# Rectifier.net
KiCad netlist of a schematic drawn in Altium Designer
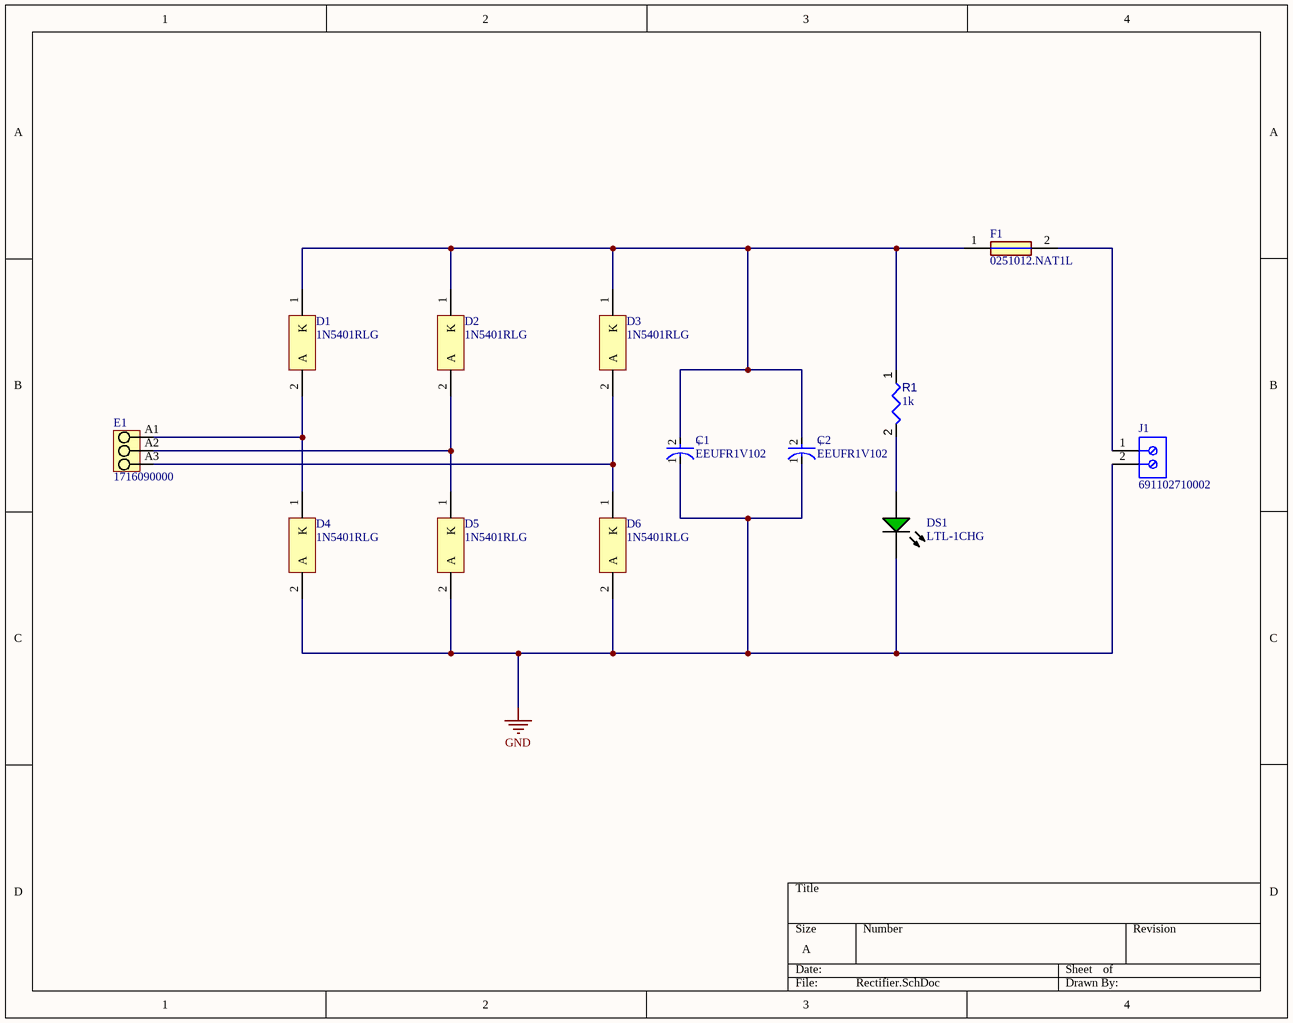
[diagram p0: Rectifier.SchDoc]

(export (version "E")
  (design (tool "Eeschema 10.0.6"))
  (components
    (comp (ref "C1")
      (value "EEUFR1V102")
      (footprint "FP-RAD-TH-D_12_5_0_5-L_20-MFG")
      (description "Aluminum Electrolytic Capacitors (Radial Lead Type) 1000uF ±20% 35V")
      (fields (field (name "TOLERANCE") "20%") (field (name "VOLTAGE") "35V"))
      (libsource (lib "Altium Content Vault") (part "a00bbbee19879c290e62620ae7e47b1"))
    )
    (comp (ref "C2")
      (value "EEUFR1V102")
      (footprint "FP-RAD-TH-D_12_5_0_5-L_20-MFG")
      (description "Aluminum Electrolytic Capacitors (Radial Lead Type) 1000uF ±20% 35V")
      (fields (field (name "TOLERANCE") "20%") (field (name "VOLTAGE") "35V"))
      (libsource (lib "Altium Content Vault") (part "a00bbbee19879c290e62620ae7e47b1"))
    )
    (comp (ref "D1")
      (value "1N5401RLG")
      (footprint "ONSC-AXIAL_LEAD-2-267-05_V")
      (description "Standard Recovery Rectifier, 2-Pin Axial_Lead, Pb-Free, Tape and Reel")
      (fields (field (name "MANUFACTURER") "On Semiconductor"))
      (libsource (lib "Altium Content Vault") (part "ONSC-D-K1A2-2_A"))
    )
    (comp (ref "D2")
      (value "1N5401RLG")
      (footprint "ONSC-AXIAL_LEAD-2-267-05_V")
      (description "Standard Recovery Rectifier, 2-Pin Axial_Lead, Pb-Free, Tape and Reel")
      (fields (field (name "MANUFACTURER") "On Semiconductor"))
      (libsource (lib "Altium Content Vault") (part "ONSC-D-K1A2-2_A"))
    )
    (comp (ref "D3")
      (value "1N5401RLG")
      (footprint "ONSC-AXIAL_LEAD-2-267-05_V")
      (description "Standard Recovery Rectifier, 2-Pin Axial_Lead, Pb-Free, Tape and Reel")
      (fields (field (name "MANUFACTURER") "On Semiconductor"))
      (libsource (lib "Altium Content Vault") (part "ONSC-D-K1A2-2_A"))
    )
    (comp (ref "D4")
      (value "1N5401RLG")
      (footprint "ONSC-AXIAL_LEAD-2-267-05_V")
      (description "Standard Recovery Rectifier, 2-Pin Axial_Lead, Pb-Free, Tape and Reel")
      (fields (field (name "MANUFACTURER") "On Semiconductor"))
      (libsource (lib "Altium Content Vault") (part "ONSC-D-K1A2-2_A"))
    )
    (comp (ref "D5")
      (value "1N5401RLG")
      (footprint "ONSC-AXIAL_LEAD-2-267-05_V")
      (description "Standard Recovery Rectifier, 2-Pin Axial_Lead, Pb-Free, Tape and Reel")
      (fields (field (name "MANUFACTURER") "On Semiconductor"))
      (libsource (lib "Altium Content Vault") (part "ONSC-D-K1A2-2_A"))
    )
    (comp (ref "D6")
      (value "1N5401RLG")
      (footprint "ONSC-AXIAL_LEAD-2-267-05_V")
      (description "Standard Recovery Rectifier, 2-Pin Axial_Lead, Pb-Free, Tape and Reel")
      (fields (field (name "MANUFACTURER") "On Semiconductor"))
      (libsource (lib "Altium Content Vault") (part "ONSC-D-K1A2-2_A"))
    )
    (comp (ref "DS1")
      (value "LTL-1CHG")
      (footprint "LTST-LTL-1CHG-2")
      (description "LED Uni-Color Green, 100 mW, 30 mA, -55 to 100 degC, 2-Pin THD, RoHS, Bulk")
      (fields (field (name "POWER") "100mW") (field (name "MANUFACTURER") "Lite-On"))
      (libsource (lib "Colton's Workspace") (part "LED-GREEN-AK-2"))
    )
    (comp (ref "E1")
      (value "1716090000")
      (footprint "LM_5_08_90_03")
      (description "OMNIMATE Signal - series LM")
      (fields (field (name "MANUFACTURER") "Weidmueller"))
      (libsource (lib "Altium Content Vault") (part "Terminal_03_1x03"))
    )
    (comp (ref "F1")
      (value "0251012.NAT1L")
      (footprint "SamacSys:0251012NAT1L")
      (description "Fuse")
      (libsource (lib "*") (part "0251012.NAT1L"))
    )
    (comp (ref "J1")
      (value "691102710002")
      (footprint "691102710002")
      (description "Series 102 - 5.00 mm Horizontal Entry Modular with Pressure Clamp WR-TBL, 2 pin")
      (fields (field (name "MANUFACTURER") "Wurth Elektronik") (field (name "PUBLISHER") "WurthElektronik"))
      (libsource (lib "Altium Content Vault") (part "WE-CN-1P-F-TB2"))
    )
    (comp (ref "R1")
      (value "1k")
      (footprint "RESA60-630X240")
      (description "Axial Resistor, 1 KOhm, +/- 1%, 250 mW, -55 to 155 degC, 2-Pin THD, RoHS, Bulk")
      (fields (field (name "TOLERANCE") "1%") (field (name "POWER") "250mW"))
      (libsource (lib "Colton's Workspace") (part "RES-2"))
    )
  )
  (nets
    (net (code "1") (name "GND") (class "Default")
      (node (ref "C1") (pin "1") (pinfunction "C_1") (pintype "passive"))
      (node (ref "C2") (pin "1") (pinfunction "C_1") (pintype "passive"))
      (node (ref "D4") (pin "2") (pinfunction "A_2") (pintype "passive"))
      (node (ref "D5") (pin "2") (pinfunction "A_2") (pintype "passive"))
      (node (ref "D6") (pin "2") (pinfunction "A_2") (pintype "passive"))
      (node (ref "DS1") (pin "2") (pinfunction "K_2") (pintype "passive"))
      (node (ref "J1") (pin "2") (pinfunction "2_2") (pintype "passive"))
    )
    (net (code "2") (name "Net-(C1-A)") (class "Default")
      (node (ref "C1") (pin "2") (pinfunction "A_2") (pintype "passive"))
      (node (ref "C2") (pin "2") (pinfunction "A_2") (pintype "passive"))
      (node (ref "D1") (pin "1") (pinfunction "K_1") (pintype "passive"))
      (node (ref "D2") (pin "1") (pinfunction "K_1") (pintype "passive"))
      (node (ref "D3") (pin "1") (pinfunction "K_1") (pintype "passive"))
      (node (ref "F1") (pin "1") (pinfunction "1_1") (pintype "passive"))
      (node (ref "R1") (pin "1") (pinfunction "1_1") (pintype "passive"))
    )
    (net (code "3") (name "Net-(D1-A)") (class "Default")
      (node (ref "D1") (pin "2") (pinfunction "A_2") (pintype "passive"))
      (node (ref "D4") (pin "1") (pinfunction "K_1") (pintype "passive"))
      (node (ref "E1") (pin "A1") (pinfunction "A1_A1") (pintype "passive"))
    )
    (net (code "4") (name "Net-(D2-A)") (class "Default")
      (node (ref "D2") (pin "2") (pinfunction "A_2") (pintype "passive"))
      (node (ref "D5") (pin "1") (pinfunction "K_1") (pintype "passive"))
      (node (ref "E1") (pin "A2") (pinfunction "A2_A2") (pintype "passive"))
    )
    (net (code "5") (name "Net-(D3-A)") (class "Default")
      (node (ref "D3") (pin "2") (pinfunction "A_2") (pintype "passive"))
      (node (ref "D6") (pin "1") (pinfunction "K_1") (pintype "passive"))
      (node (ref "E1") (pin "A3") (pinfunction "A3_A3") (pintype "passive"))
    )
    (net (code "6") (name "Net-(DS1-A)") (class "Default")
      (node (ref "DS1") (pin "1") (pinfunction "A_1") (pintype "passive"))
      (node (ref "R1") (pin "2") (pinfunction "2_2") (pintype "passive"))
    )
    (net (code "7") (name "Net-(F1-Pad2)") (class "Default")
      (node (ref "F1") (pin "2") (pinfunction "2_2") (pintype "passive"))
      (node (ref "J1") (pin "1") (pinfunction "1_1") (pintype "passive"))
    )
  )
)
